# AmplifyEmit.net
KiCad netlist of a schematic drawn in Altium Designer
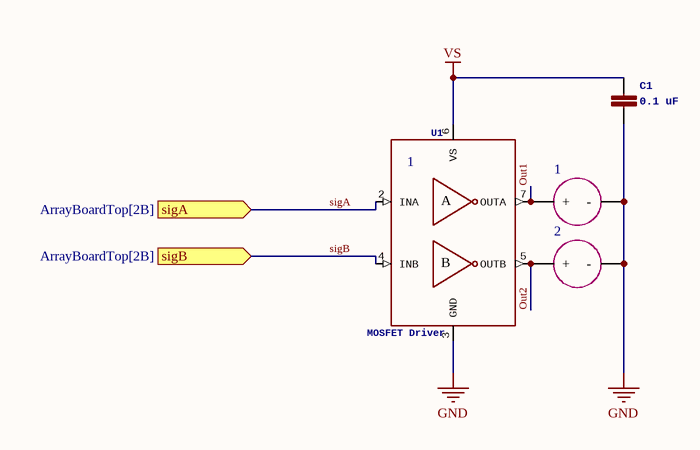
[diagram p0: AmplifyEmit.SchDoc]

(export (version "E")
  (design (tool "Eeschema 10.0.6"))
  (components
    (comp (ref "1") (value "EMIT") (footprint "TRANSDUCER") (libsource (lib "InteractLab") (part "EMIT")))
    (comp (ref "2") (value "EMIT") (footprint "TRANSDUCER") (libsource (lib "InteractLab") (part "EMIT")))
    (comp (ref "C1")
      (value "0.1 uF")
      (footprint "CAP0805 - CERAMIC")
      (libsource (lib "InteractLab") (part "CAP CERAMIC"))
    )
    (comp (ref "U1")
      (value "MOSFET Driver")
      (footprint "MIC4127YME")
      (libsource (lib "InteractLab") (part "MIC4127"))
    )
  )
  (nets
    (net (code "1") (name "/Out1") (class "Default")
      (node (ref "1") (pin "+") (pinfunction "+_+") (pintype "passive"))
      (node (ref "U1") (pin "7") (pinfunction "OUTA_7") (pintype "output"))
    )
    (net (code "2") (name "/Out2") (class "Default")
      (node (ref "2") (pin "+") (pinfunction "+_+") (pintype "passive"))
      (node (ref "U1") (pin "5") (pinfunction "OUTB_5") (pintype "output"))
    )
    (net (code "3") (name "/sigA") (class "Default")
      (node (ref "U1") (pin "2") (pinfunction "INA_2") (pintype "input"))
    )
    (net (code "4") (name "/sigB") (class "Default")
      (node (ref "U1") (pin "4") (pinfunction "INB_4") (pintype "input"))
    )
    (net (code "5") (name "GND") (class "Default")
      (node (ref "1") (pin "-") (pinfunction "-_-") (pintype "passive"))
      (node (ref "2") (pin "-") (pinfunction "-_-") (pintype "passive"))
      (node (ref "C1") (pin "2") (pinfunction "2_2") (pintype "passive"))
      (node (ref "U1") (pin "3") (pinfunction "GND_3") (pintype "power_in"))
    )
    (net (code "6") (name "VS") (class "Default")
      (node (ref "C1") (pin "1") (pinfunction "1_1") (pintype "passive"))
      (node (ref "U1") (pin "6") (pinfunction "VS_6") (pintype "power_in"))
    )
  )
)
